# SD_Card.net
KiCad netlist of a schematic drawn in Altium Designer
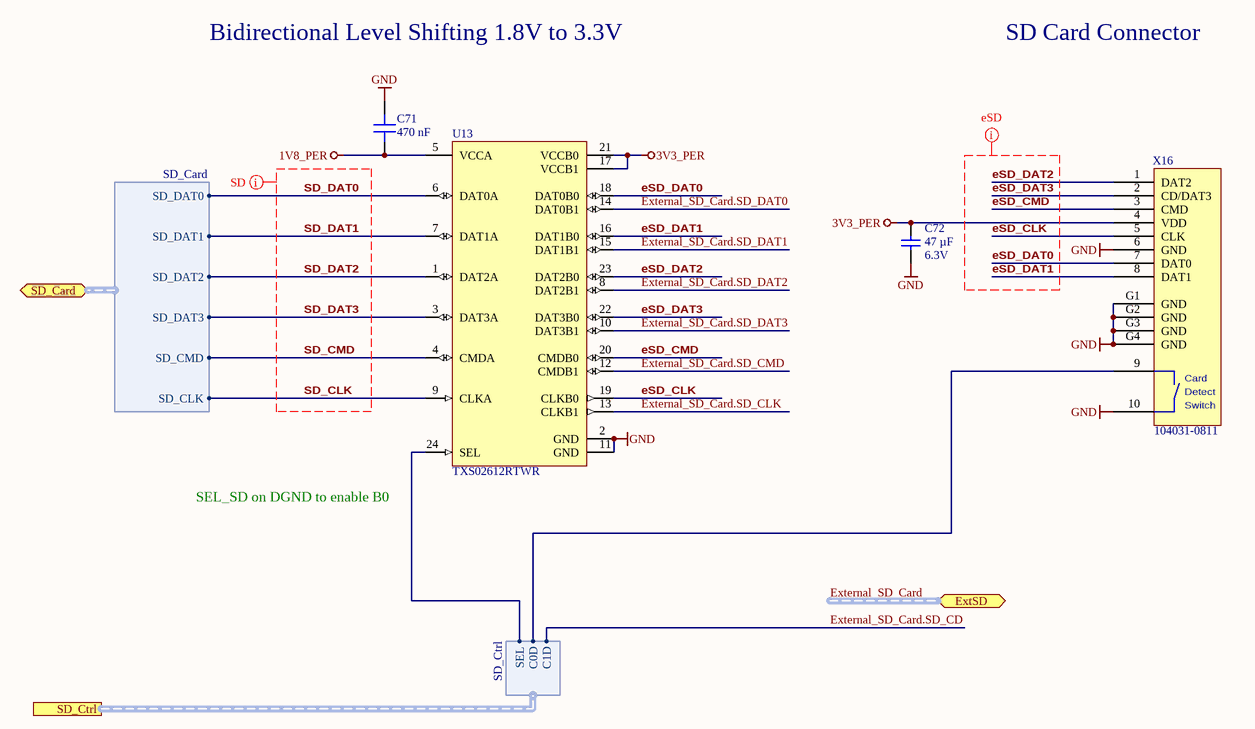
[diagram p0: SD_Card.SchDoc]

(export (version "E")
  (design (tool "Eeschema 10.0.6"))
  (components
    (comp (ref "C71")
      (value "470 nF")
      (footprint "C_0603_TE")
      (description "Capacitor 0603, 50 VDC, 470 nF, X5R")
      (fields
        (field (name "MANUFACTURER PART NUMBER") "CL10A474KB8NNNC")
        (field (name "MANUFACTURER") "Samsung Electro-Mechanics")
        (field (name "CREATED FROM") "AGeiger")
      )
      (libsource (lib "user") (part "Capacitor"))
    )
    (comp (ref "C72")
      (value "47 µF")
      (footprint "C_0805_TE")
      (description "Generic capacitor")
      (fields
        (field (name "TOLERANCE") "10 %")
        (field (name "VOLTAGE") "6.3V")
        (field (name "MANUFACTURER PART NUMBER") "UZgen_C_0805_47uF_6.3V_X7R")
        (field (name "CREATED FROM") "UZgenTool")
      )
      (libsource (lib "user") (part "CAP-NP"))
    )
    (comp (ref "U13")
      (value "TXS02612RTWR")
      (footprint "QFN50P400X400X80-25N-255")
      (description "SDIO Port Expander with voltage level Translation")
      (fields
        (field (name "MANUFACTURER") "Texas Instruments")
        (field (name "LCSC PART NUMBER") "C140276")
        (field (name "CREATED FROM") "MGremer")
      )
      (libsource (lib "user") (part "TXS02612RTWR"))
    )
    (comp (ref "X16")
      (value "104031-0811")
      (footprint "104031-0811")
      (description "microSD Memory Card Connector with detect switch")
      (fields
        (field (name "MANUFACTURER") "Molex")
        (field (name "LCSC PART NUMBER") "C585350")
        (field (name "CREATED FROM") "MGremer")
      )
      (libsource (lib "user") (part "104031-0811"))
    )
  )
  (nets
    (net (code "4") (name "/External_SD_Card.SD_CD") (class "Default")
      (node (ref "X16") (pin "9") (pinfunction "CDSW_9") (pintype "passive"))
    )
    (net (code "5") (name "/External_SD_Card.SD_CLK") (class "Default")
      (node (ref "U13") (pin "13") (pinfunction "CLKB1_13") (pintype "output"))
    )
    (net (code "6") (name "/External_SD_Card.SD_CMD") (class "Default")
      (node (ref "U13") (pin "12") (pinfunction "CMDB1_12") (pintype "bidirectional"))
    )
    (net (code "7") (name "/External_SD_Card.SD_DAT0") (class "Default")
      (node (ref "U13") (pin "14") (pinfunction "DAT0B1_14") (pintype "bidirectional"))
    )
    (net (code "8") (name "/External_SD_Card.SD_DAT1") (class "Default")
      (node (ref "U13") (pin "15") (pinfunction "DAT1B1_15") (pintype "bidirectional"))
    )
    (net (code "9") (name "/External_SD_Card.SD_DAT2") (class "Default")
      (node (ref "U13") (pin "8") (pinfunction "DAT2B1_8") (pintype "bidirectional"))
    )
    (net (code "10") (name "/External_SD_Card.SD_DAT3") (class "Default")
      (node (ref "U13") (pin "10") (pinfunction "DAT3B1_10") (pintype "bidirectional"))
    )
    (net (code "11") (name "/SD_CLK") (class "Default")
      (node (ref "U13") (pin "9") (pinfunction "CLKA_9") (pintype "input"))
    )
    (net (code "12") (name "/SD_CMD") (class "Default")
      (node (ref "U13") (pin "4") (pinfunction "CMDA_4") (pintype "bidirectional"))
    )
    (net (code "13") (name "/SD_DAT0") (class "Default")
      (node (ref "U13") (pin "6") (pinfunction "DAT0A_6") (pintype "bidirectional"))
    )
    (net (code "14") (name "/SD_DAT1") (class "Default")
      (node (ref "U13") (pin "7") (pinfunction "DAT1A_7") (pintype "bidirectional"))
    )
    (net (code "15") (name "/SD_DAT2") (class "Default")
      (node (ref "U13") (pin "1") (pinfunction "DAT2A_1") (pintype "bidirectional"))
    )
    (net (code "16") (name "/SD_DAT3") (class "Default")
      (node (ref "U13") (pin "3") (pinfunction "DAT3A_3") (pintype "bidirectional"))
    )
    (net (code "17") (name "/eSD_CLK") (class "Default")
      (node (ref "U13") (pin "19") (pinfunction "CLKB0_19") (pintype "output"))
      (node (ref "X16") (pin "5") (pinfunction "CLK_5") (pintype "passive"))
    )
    (net (code "18") (name "/eSD_CMD") (class "Default")
      (node (ref "U13") (pin "20") (pinfunction "CMDB0_20") (pintype "bidirectional"))
      (node (ref "X16") (pin "3") (pinfunction "CMD_3") (pintype "passive"))
    )
    (net (code "19") (name "/eSD_DAT0") (class "Default")
      (node (ref "U13") (pin "18") (pinfunction "DAT0B0_18") (pintype "bidirectional"))
      (node (ref "X16") (pin "7") (pinfunction "DAT0_7") (pintype "passive"))
    )
    (net (code "20") (name "/eSD_DAT1") (class "Default")
      (node (ref "U13") (pin "16") (pinfunction "DAT1B0_16") (pintype "bidirectional"))
      (node (ref "X16") (pin "8") (pinfunction "DAT1_8") (pintype "passive"))
    )
    (net (code "21") (name "/eSD_DAT2") (class "Default")
      (node (ref "U13") (pin "23") (pinfunction "DAT2B0_23") (pintype "bidirectional"))
      (node (ref "X16") (pin "1") (pinfunction "DAT2_1") (pintype "passive"))
    )
    (net (code "22") (name "/eSD_DAT3") (class "Default")
      (node (ref "U13") (pin "22") (pinfunction "DAT3B0_22") (pintype "bidirectional"))
      (node (ref "X16") (pin "2") (pinfunction "CD/DAT3_2") (pintype "passive"))
    )
    (net (code "26") (name "1V8_PER") (class "Default")
      (node (ref "C71") (pin "1") (pinfunction "1_1") (pintype "passive"))
      (node (ref "U13") (pin "5") (pinfunction "VCCA_5") (pintype "power_in"))
    )
    (net (code "27") (name "3V3_PER") (class "Default")
      (node (ref "C72") (pin "2") (pinfunction "2_2") (pintype "passive"))
      (node (ref "U13") (pin "17") (pinfunction "VCCB1_17") (pintype "power_in"))
      (node (ref "U13") (pin "21") (pinfunction "VCCB0_21") (pintype "power_in"))
      (node (ref "X16") (pin "4") (pinfunction "VDD_4") (pintype "passive"))
    )
    (net (code "28") (name "GND") (class "Default")
      (node (ref "C71") (pin "2") (pinfunction "2_2") (pintype "passive"))
      (node (ref "C72") (pin "1") (pinfunction "1_1") (pintype "passive"))
      (node (ref "U13") (pin "11") (pinfunction "GND_11") (pintype "power_in"))
      (node (ref "U13") (pin "2") (pinfunction "GND_2") (pintype "power_in"))
      (node (ref "X16") (pin "10") (pinfunction "CDSW_10") (pintype "passive"))
      (node (ref "X16") (pin "6") (pinfunction "GND_6") (pintype "passive"))
      (node (ref "X16") (pin "G1") (pinfunction "GND_G1") (pintype "passive"))
      (node (ref "X16") (pin "G2") (pinfunction "GND_G2") (pintype "passive"))
      (node (ref "X16") (pin "G3") (pinfunction "GND_G3") (pintype "passive"))
      (node (ref "X16") (pin "G4") (pinfunction "GND_G4") (pintype "passive"))
    )
    (net (code "29") (name "unconnected-(U13-SEL-Pad24)") (class "Default")
      (node (ref "U13") (pin "24") (pinfunction "SEL_24") (pintype "input"))
    )
  )
)
